# Sheet_3.net
KiCad netlist of a schematic drawn in EasyEDA
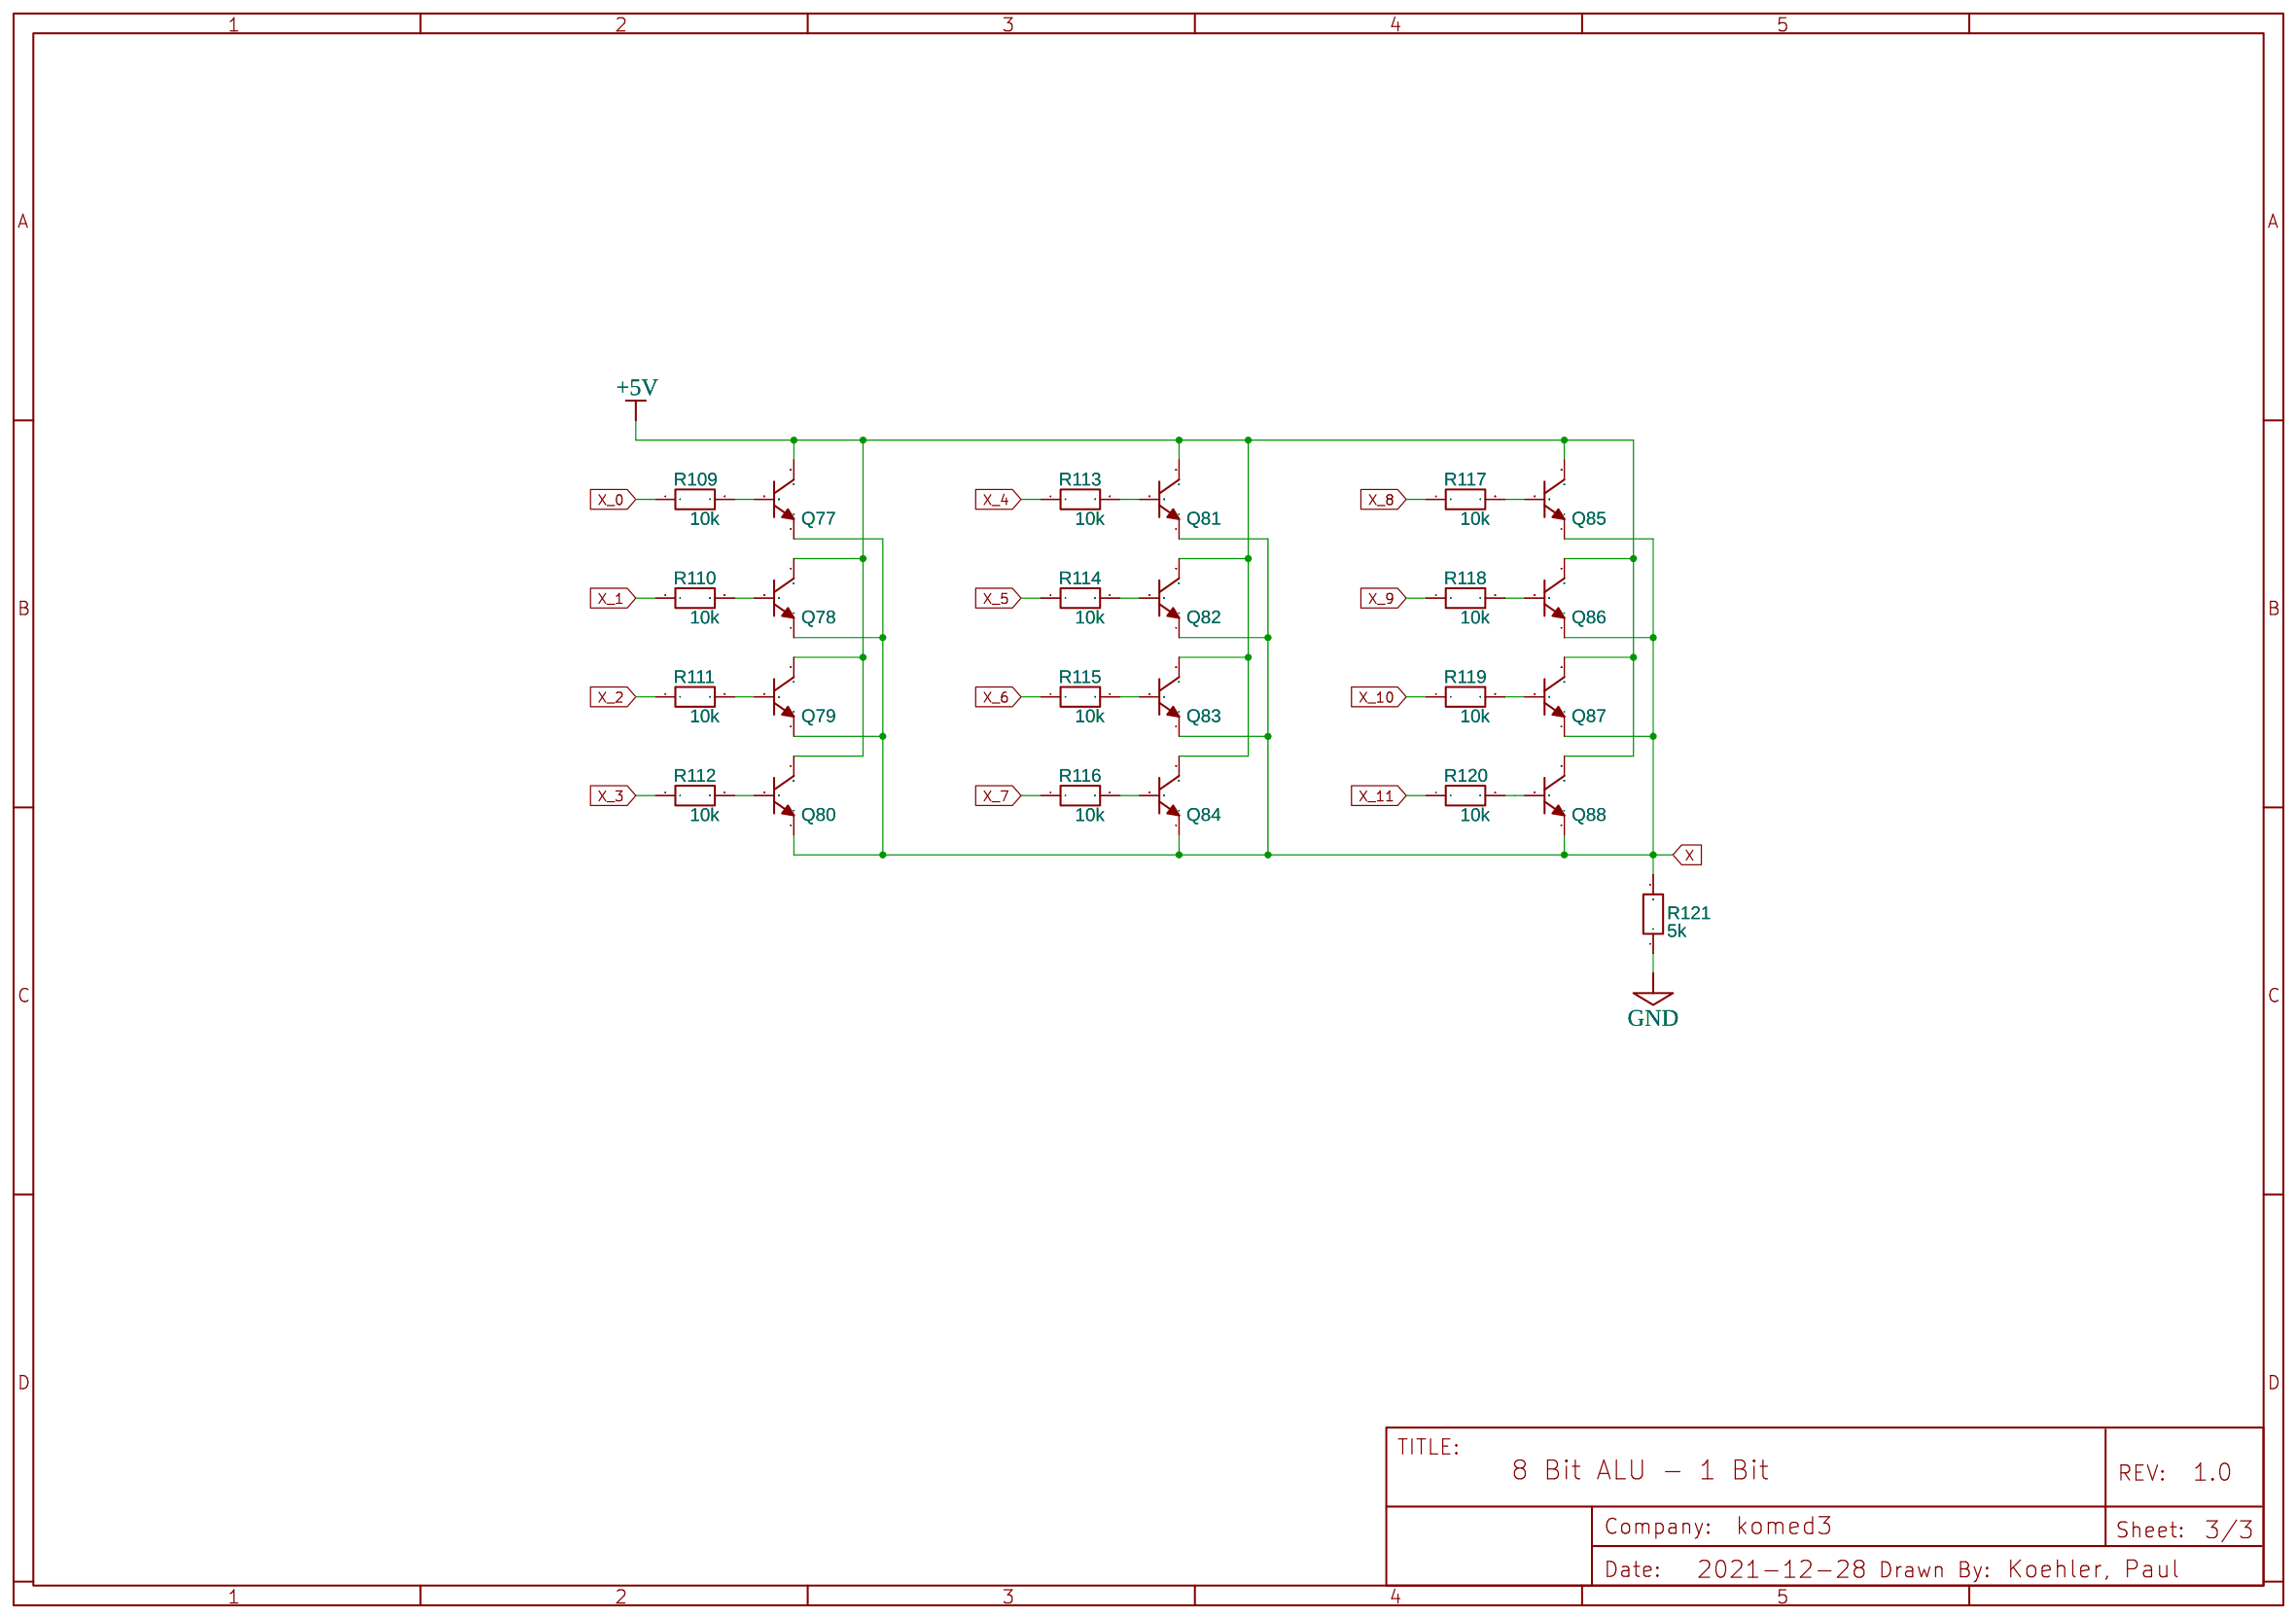
[diagram p0: schematic sheet]

(export (version "E")
  (design (tool "Eeschema 10.0.6"))
  (components
    (comp (ref "Q77")
      (value "2N3904(TO-92)")
      (fields (field (name "BOM_Manufacturer Part") "2N3904") (field (name "BOM_Supplier Part") "C118538"))
      (libsource (lib "") (part "2N3904(TO-92)"))
    )
    (comp (ref "Q78")
      (value "2N3904(TO-92)")
      (fields (field (name "BOM_Manufacturer Part") "2N3904") (field (name "BOM_Supplier Part") "C118538"))
      (libsource (lib "") (part "2N3904(TO-92)"))
    )
    (comp (ref "Q79")
      (value "2N3904(TO-92)")
      (fields (field (name "BOM_Manufacturer Part") "2N3904") (field (name "BOM_Supplier Part") "C118538"))
      (libsource (lib "") (part "2N3904(TO-92)"))
    )
    (comp (ref "Q80")
      (value "2N3904(TO-92)")
      (fields (field (name "BOM_Manufacturer Part") "2N3904") (field (name "BOM_Supplier Part") "C118538"))
      (libsource (lib "") (part "2N3904(TO-92)"))
    )
    (comp (ref "Q81")
      (value "2N3904(TO-92)")
      (fields (field (name "BOM_Manufacturer Part") "2N3904") (field (name "BOM_Supplier Part") "C118538"))
      (libsource (lib "") (part "2N3904(TO-92)"))
    )
    (comp (ref "Q82")
      (value "2N3904(TO-92)")
      (fields (field (name "BOM_Manufacturer Part") "2N3904") (field (name "BOM_Supplier Part") "C118538"))
      (libsource (lib "") (part "2N3904(TO-92)"))
    )
    (comp (ref "Q83")
      (value "2N3904(TO-92)")
      (fields (field (name "BOM_Manufacturer Part") "2N3904") (field (name "BOM_Supplier Part") "C118538"))
      (libsource (lib "") (part "2N3904(TO-92)"))
    )
    (comp (ref "Q84")
      (value "2N3904(TO-92)")
      (fields (field (name "BOM_Manufacturer Part") "2N3904") (field (name "BOM_Supplier Part") "C118538"))
      (libsource (lib "") (part "2N3904(TO-92)"))
    )
    (comp (ref "Q85")
      (value "2N3904(TO-92)")
      (fields (field (name "BOM_Manufacturer Part") "2N3904") (field (name "BOM_Supplier Part") "C118538"))
      (libsource (lib "") (part "2N3904(TO-92)"))
    )
    (comp (ref "Q86")
      (value "2N3904(TO-92)")
      (fields (field (name "BOM_Manufacturer Part") "2N3904") (field (name "BOM_Supplier Part") "C118538"))
      (libsource (lib "") (part "2N3904(TO-92)"))
    )
    (comp (ref "Q87")
      (value "2N3904(TO-92)")
      (fields (field (name "BOM_Manufacturer Part") "2N3904") (field (name "BOM_Supplier Part") "C118538"))
      (libsource (lib "") (part "2N3904(TO-92)"))
    )
    (comp (ref "Q88")
      (value "2N3904(TO-92)")
      (fields (field (name "BOM_Manufacturer Part") "2N3904") (field (name "BOM_Supplier Part") "C118538"))
      (libsource (lib "") (part "2N3904(TO-92)"))
    )
    (comp (ref "R109") (value "10k") (libsource (lib "") (part "R_AXIAL-0.3_EU")))
    (comp (ref "R110") (value "10k") (libsource (lib "") (part "R_AXIAL-0.3_EU")))
    (comp (ref "R111") (value "10k") (libsource (lib "") (part "R_AXIAL-0.3_EU")))
    (comp (ref "R112") (value "10k") (libsource (lib "") (part "R_AXIAL-0.3_EU")))
    (comp (ref "R113") (value "10k") (libsource (lib "") (part "R_AXIAL-0.3_EU")))
    (comp (ref "R114") (value "10k") (libsource (lib "") (part "R_AXIAL-0.3_EU")))
    (comp (ref "R115") (value "10k") (libsource (lib "") (part "R_AXIAL-0.3_EU")))
    (comp (ref "R116") (value "10k") (libsource (lib "") (part "R_AXIAL-0.3_EU")))
    (comp (ref "R117") (value "10k") (libsource (lib "") (part "R_AXIAL-0.3_EU")))
    (comp (ref "R118") (value "10k") (libsource (lib "") (part "R_AXIAL-0.3_EU")))
    (comp (ref "R119") (value "10k") (libsource (lib "") (part "R_AXIAL-0.3_EU")))
    (comp (ref "R120") (value "10k") (libsource (lib "") (part "R_AXIAL-0.3_EU")))
    (comp (ref "R121") (value "5k") (libsource (lib "") (part "R_AXIAL-0.3_EU_1")))
  )
  (nets
    (net (code "1") (name "+5V") (class "Default")
      (node (ref "Q77") (pin "3") (pinfunction "C_3") (pintype "unspecified"))
      (node (ref "Q78") (pin "3") (pinfunction "C_3") (pintype "unspecified"))
      (node (ref "Q79") (pin "3") (pinfunction "C_3") (pintype "unspecified"))
      (node (ref "Q80") (pin "3") (pinfunction "C_3") (pintype "unspecified"))
      (node (ref "Q81") (pin "3") (pinfunction "C_3") (pintype "unspecified"))
      (node (ref "Q82") (pin "3") (pinfunction "C_3") (pintype "unspecified"))
      (node (ref "Q83") (pin "3") (pinfunction "C_3") (pintype "unspecified"))
      (node (ref "Q84") (pin "3") (pinfunction "C_3") (pintype "unspecified"))
      (node (ref "Q85") (pin "3") (pinfunction "C_3") (pintype "unspecified"))
      (node (ref "Q86") (pin "3") (pinfunction "C_3") (pintype "unspecified"))
      (node (ref "Q87") (pin "3") (pinfunction "C_3") (pintype "unspecified"))
      (node (ref "Q88") (pin "3") (pinfunction "C_3") (pintype "unspecified"))
    )
    (net (code "2") (name "GND") (class "Default")
      (node (ref "R121") (pin "1") (pinfunction "1_1") (pintype "unspecified"))
    )
    (net (code "3") (name "Net-(Q77-B)") (class "Default")
      (node (ref "Q77") (pin "2") (pinfunction "B_2") (pintype "unspecified"))
      (node (ref "R109") (pin "2") (pinfunction "2_2") (pintype "unspecified"))
    )
    (net (code "4") (name "Net-(Q78-B)") (class "Default")
      (node (ref "Q78") (pin "2") (pinfunction "B_2") (pintype "unspecified"))
      (node (ref "R110") (pin "2") (pinfunction "2_2") (pintype "unspecified"))
    )
    (net (code "5") (name "Net-(Q79-B)") (class "Default")
      (node (ref "Q79") (pin "2") (pinfunction "B_2") (pintype "unspecified"))
      (node (ref "R111") (pin "2") (pinfunction "2_2") (pintype "unspecified"))
    )
    (net (code "6") (name "Net-(Q80-B)") (class "Default")
      (node (ref "Q80") (pin "2") (pinfunction "B_2") (pintype "unspecified"))
      (node (ref "R112") (pin "2") (pinfunction "2_2") (pintype "unspecified"))
    )
    (net (code "7") (name "Net-(Q81-B)") (class "Default")
      (node (ref "Q81") (pin "2") (pinfunction "B_2") (pintype "unspecified"))
      (node (ref "R113") (pin "2") (pinfunction "2_2") (pintype "unspecified"))
    )
    (net (code "8") (name "Net-(Q82-B)") (class "Default")
      (node (ref "Q82") (pin "2") (pinfunction "B_2") (pintype "unspecified"))
      (node (ref "R114") (pin "2") (pinfunction "2_2") (pintype "unspecified"))
    )
    (net (code "9") (name "Net-(Q83-B)") (class "Default")
      (node (ref "Q83") (pin "2") (pinfunction "B_2") (pintype "unspecified"))
      (node (ref "R115") (pin "2") (pinfunction "2_2") (pintype "unspecified"))
    )
    (net (code "10") (name "Net-(Q84-B)") (class "Default")
      (node (ref "Q84") (pin "2") (pinfunction "B_2") (pintype "unspecified"))
      (node (ref "R116") (pin "2") (pinfunction "2_2") (pintype "unspecified"))
    )
    (net (code "11") (name "Net-(Q85-B)") (class "Default")
      (node (ref "Q85") (pin "2") (pinfunction "B_2") (pintype "unspecified"))
      (node (ref "R117") (pin "2") (pinfunction "2_2") (pintype "unspecified"))
    )
    (net (code "12") (name "Net-(Q86-B)") (class "Default")
      (node (ref "Q86") (pin "2") (pinfunction "B_2") (pintype "unspecified"))
      (node (ref "R118") (pin "2") (pinfunction "2_2") (pintype "unspecified"))
    )
    (net (code "13") (name "Net-(Q87-B)") (class "Default")
      (node (ref "Q87") (pin "2") (pinfunction "B_2") (pintype "unspecified"))
      (node (ref "R119") (pin "2") (pinfunction "2_2") (pintype "unspecified"))
    )
    (net (code "14") (name "Net-(Q88-B)") (class "Default")
      (node (ref "Q88") (pin "2") (pinfunction "B_2") (pintype "unspecified"))
      (node (ref "R120") (pin "2") (pinfunction "2_2") (pintype "unspecified"))
    )
    (net (code "15") (name "X") (class "Default")
      (node (ref "Q77") (pin "1") (pinfunction "E_1") (pintype "unspecified"))
      (node (ref "Q78") (pin "1") (pinfunction "E_1") (pintype "unspecified"))
      (node (ref "Q79") (pin "1") (pinfunction "E_1") (pintype "unspecified"))
      (node (ref "Q80") (pin "1") (pinfunction "E_1") (pintype "unspecified"))
      (node (ref "Q81") (pin "1") (pinfunction "E_1") (pintype "unspecified"))
      (node (ref "Q82") (pin "1") (pinfunction "E_1") (pintype "unspecified"))
      (node (ref "Q83") (pin "1") (pinfunction "E_1") (pintype "unspecified"))
      (node (ref "Q84") (pin "1") (pinfunction "E_1") (pintype "unspecified"))
      (node (ref "Q85") (pin "1") (pinfunction "E_1") (pintype "unspecified"))
      (node (ref "Q86") (pin "1") (pinfunction "E_1") (pintype "unspecified"))
      (node (ref "Q87") (pin "1") (pinfunction "E_1") (pintype "unspecified"))
      (node (ref "Q88") (pin "1") (pinfunction "E_1") (pintype "unspecified"))
      (node (ref "R121") (pin "2") (pinfunction "2_2") (pintype "unspecified"))
    )
    (net (code "16") (name "X_0") (class "Default")
      (node (ref "R109") (pin "1") (pinfunction "1_1") (pintype "unspecified"))
    )
    (net (code "17") (name "X_1") (class "Default")
      (node (ref "R110") (pin "1") (pinfunction "1_1") (pintype "unspecified"))
    )
    (net (code "18") (name "X_2") (class "Default")
      (node (ref "R111") (pin "1") (pinfunction "1_1") (pintype "unspecified"))
    )
    (net (code "19") (name "X_3") (class "Default")
      (node (ref "R112") (pin "1") (pinfunction "1_1") (pintype "unspecified"))
    )
    (net (code "20") (name "X_4") (class "Default")
      (node (ref "R113") (pin "1") (pinfunction "1_1") (pintype "unspecified"))
    )
    (net (code "21") (name "X_5") (class "Default")
      (node (ref "R114") (pin "1") (pinfunction "1_1") (pintype "unspecified"))
    )
    (net (code "22") (name "X_6") (class "Default")
      (node (ref "R115") (pin "1") (pinfunction "1_1") (pintype "unspecified"))
    )
    (net (code "23") (name "X_7") (class "Default")
      (node (ref "R116") (pin "1") (pinfunction "1_1") (pintype "unspecified"))
    )
    (net (code "24") (name "X_8") (class "Default")
      (node (ref "R117") (pin "1") (pinfunction "1_1") (pintype "unspecified"))
    )
    (net (code "25") (name "X_9") (class "Default")
      (node (ref "R118") (pin "1") (pinfunction "1_1") (pintype "unspecified"))
    )
    (net (code "26") (name "X_10") (class "Default")
      (node (ref "R119") (pin "1") (pinfunction "1_1") (pintype "unspecified"))
    )
    (net (code "27") (name "X_11") (class "Default")
      (node (ref "R120") (pin "1") (pinfunction "1_1") (pintype "unspecified"))
    )
  )
)
